# ESP32_Module.net
KiCad netlist of a schematic drawn in Altium Designer
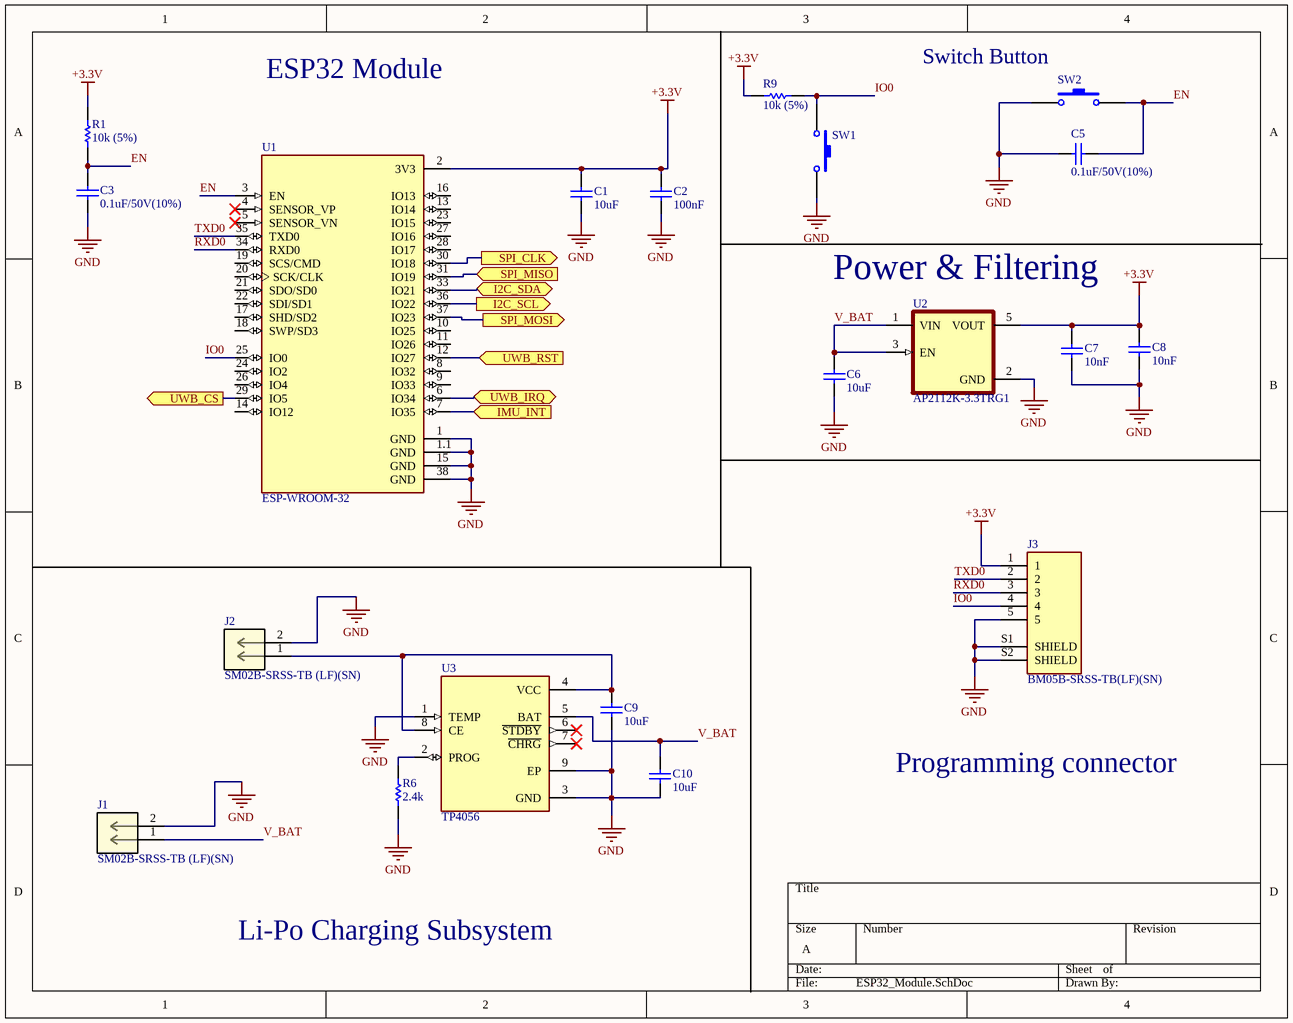
[diagram p0: ESP32_Module.SchDoc]

(export (version "E")
  (design (tool "Eeschema 10.0.6"))
  (components
    (comp (ref "C1")
      (value "10uF")
      (footprint "CAPC1608X90")
      (description "Capacitor")
      (fields (field (name "Comment") "Cap") (field (name "PUBLISHER") "Altium Limited"))
      (libsource (lib "Miscellaneous Devices") (part "Cap"))
    )
    (comp (ref "C2")
      (value "100nF")
      (footprint "CAPC1005X55N")
      (description "Capacitor")
      (fields (field (name "Comment") "Cap") (field (name "PUBLISHER") "Altium Limited"))
      (libsource (lib "Miscellaneous Devices") (part "Cap"))
    )
    (comp (ref "C3")
      (value "0.1uF/50V(10%)")
      (footprint "CAPC2012X94N")
      (description "Capacitor")
      (fields (field (name "Comment") "Cap") (field (name "PUBLISHER") "Altium Limited"))
      (libsource (lib "Miscellaneous Devices") (part "Cap"))
    )
    (comp (ref "C5")
      (value "0.1uF/50V(10%)")
      (footprint "CAPC2012X94N")
      (description "Capacitor")
      (fields (field (name "Comment") "Cap") (field (name "PUBLISHER") "Altium Limited"))
      (libsource (lib "Miscellaneous Devices") (part "Cap"))
    )
    (comp (ref "C6")
      (value "10uF")
      (footprint "CAPC1608X90")
      (description "Capacitor")
      (fields (field (name "Comment") "Cap") (field (name "PUBLISHER") "Altium Limited"))
      (libsource (lib "Miscellaneous Devices") (part "Cap"))
    )
    (comp (ref "C7")
      (value "10nF")
      (footprint "CAPC1608X87N")
      (description "Capacitor")
      (fields (field (name "Comment") "Cap") (field (name "PUBLISHER") "Altium Limited"))
      (libsource (lib "Miscellaneous Devices") (part "Cap"))
    )
    (comp (ref "C8")
      (value "10nF")
      (footprint "CAPC1608X87N")
      (description "Capacitor")
      (fields (field (name "Comment") "Cap") (field (name "PUBLISHER") "Altium Limited"))
      (libsource (lib "Miscellaneous Devices") (part "Cap"))
    )
    (comp (ref "C9")
      (value "10uF")
      (footprint "CAPC1608X90")
      (description "Capacitor")
      (fields (field (name "Comment") "Cap") (field (name "PUBLISHER") "Altium Limited"))
      (libsource (lib "Miscellaneous Devices") (part "Cap"))
    )
    (comp (ref "C10")
      (value "10uF")
      (footprint "CAPC1608X90")
      (description "Capacitor")
      (fields (field (name "Comment") "Cap") (field (name "PUBLISHER") "Altium Limited"))
      (libsource (lib "Miscellaneous Devices") (part "Cap"))
    )
    (comp (ref "J1")
      (value "SM02B-SRSS-TB (LF)(SN)")
      (footprint "CONN_SM02B-SRSS-TB_JST")
      (description "Description")
      (fields (field (name "COPYRIGHT") "Copyright (C) 2026 Ultra Librarian. All rights reserved."))
      (libsource (lib "SM02B-SRSS-TBLFSN") (part "SM02B-SRSS-TB LFSN"))
    )
    (comp (ref "J2")
      (value "SM02B-SRSS-TB (LF)(SN)")
      (footprint "CONN_SM02B-SRSS-TB_JST")
      (description "Description")
      (fields (field (name "COPYRIGHT") "Copyright (C) 2026 Ultra Librarian. All rights reserved."))
      (libsource (lib "SM02B-SRSS-TBLFSN") (part "SM02B-SRSS-TB LFSN"))
    )
    (comp (ref "J3")
      (value "BM05B-SRSS-TB(LF)(SN)")
      (footprint "JST_BM05B-SRSS-TB(LF)(SN)")
      (libsource (lib "BM05B-SRSS-TB_LF__SN_") (part "BM05B-SRSS-TB(LF)(SN)"))
    )
    (comp (ref "R1")
      (value "10k (5%)")
      (footprint "RESC1005X40")
      (description "Resistor")
      (fields (field (name "Comment") "Res1") (field (name "PUBLISHER") "Altium Limited"))
      (libsource (lib "Miscellaneous Devices") (part "Res1"))
    )
    (comp (ref "R6")
      (value "2.4k")
      (footprint "RESC1005X40N")
      (description "Resistor")
      (fields (field (name "Comment") "Res1") (field (name "PUBLISHER") "Altium Limited"))
      (libsource (lib "Miscellaneous Devices") (part "Res1"))
    )
    (comp (ref "R9")
      (value "10k (5%)")
      (footprint "RESC1005X40")
      (description "Resistor")
      (fields (field (name "Comment") "Res1") (field (name "PUBLISHER") "Altium Limited"))
      (libsource (lib "Miscellaneous Devices") (part "Res1"))
    )
    (comp (ref "SW1")
      (value "SW-PB")
      (footprint "SW_TL3342F160QG")
      (description "Switch")
      (fields (field (name "PUBLISHER") "Altium Limited"))
      (libsource (lib "Miscellaneous Devices") (part "SW-PB"))
    )
    (comp (ref "SW2")
      (value "SW-PB")
      (footprint "SW_TL3342F160QG")
      (description "Switch")
      (fields (field (name "PUBLISHER") "Altium Limited"))
      (libsource (lib "Miscellaneous Devices") (part "SW-PB"))
    )
    (comp (ref "U1")
      (value "ESP-WROOM-32")
      (footprint "MODULE_ESP-WROOM-32")
      (fields (field (name "MF") "Espressif Systems"))
      (libsource (lib "ESP-WROOM-32") (part "ESP-WROOM-32"))
    )
    (comp (ref "U2")
      (value "AP2112K-3.3TRG1")
      (footprint "SOT95P285X140-5N")
      (description "Linear Voltage Regulator IC Positive Fixed 1 Output 600mA SOT-25")
      (fields (field (name "MF") "Diodes Inc."))
      (libsource (lib "AP2112K-3.3TRG1") (part "AP2112K-3.3TRG1"))
    )
    (comp (ref "U3")
      (value "TP4056")
      (footprint "SOP127P600X175-9N")
      (description "Complete single cell Li-Ion battery with a constant current / constant voltage linear charger")
      (fields (field (name "MF") "NanJing Top Power ASIC Corp."))
      (libsource (lib "TP4056") (part "TP4056"))
    )
  )
  (nets
    (net (code "1") (name "+3.3V") (class "Default")
      (node (ref "C1") (pin "2") (pinfunction "2_2") (pintype "passive"))
      (node (ref "C2") (pin "2") (pinfunction "2_2") (pintype "passive"))
      (node (ref "C7") (pin "2") (pinfunction "2_2") (pintype "passive"))
      (node (ref "C8") (pin "2") (pinfunction "2_2") (pintype "passive"))
      (node (ref "J3") (pin "1") (pinfunction "1_1") (pintype "passive"))
      (node (ref "R1") (pin "2") (pinfunction "2_2") (pintype "passive"))
      (node (ref "R9") (pin "2") (pinfunction "2_2") (pintype "passive"))
      (node (ref "U1") (pin "2") (pinfunction "3V3_2") (pintype "power_in"))
      (node (ref "U2") (pin "5") (pinfunction "VOUT_5") (pintype "power_in"))
    )
    (net (code "2") (name "/EN") (class "Default")
      (node (ref "C3") (pin "2") (pinfunction "2_2") (pintype "passive"))
      (node (ref "C5") (pin "2") (pinfunction "2_2") (pintype "passive"))
      (node (ref "R1") (pin "1") (pinfunction "1_1") (pintype "passive"))
      (node (ref "SW2") (pin "2") (pinfunction "2_2") (pintype "passive"))
      (node (ref "U1") (pin "3") (pinfunction "EN_3") (pintype "input"))
    )
    (net (code "3") (name "/I2C_SCL") (class "Default")
      (node (ref "U1") (pin "36") (pinfunction "IO22_36") (pintype "bidirectional"))
    )
    (net (code "4") (name "/I2C_SDA") (class "Default")
      (node (ref "U1") (pin "33") (pinfunction "IO21_33") (pintype "bidirectional"))
    )
    (net (code "5") (name "/IMU_INT") (class "Default")
      (node (ref "U1") (pin "7") (pinfunction "IO35_7") (pintype "bidirectional"))
    )
    (net (code "6") (name "/IO0") (class "Default")
      (node (ref "J3") (pin "4") (pinfunction "4_4") (pintype "passive"))
      (node (ref "R9") (pin "1") (pinfunction "1_1") (pintype "passive"))
      (node (ref "SW1") (pin "1") (pinfunction "1_1") (pintype "passive"))
      (node (ref "U1") (pin "25") (pinfunction "IO0_25") (pintype "bidirectional"))
    )
    (net (code "7") (name "/RXD0") (class "Default")
      (node (ref "J3") (pin "3") (pinfunction "3_3") (pintype "passive"))
      (node (ref "U1") (pin "34") (pinfunction "RXD0_34") (pintype "bidirectional"))
    )
    (net (code "8") (name "/SPI_CLK") (class "Default")
      (node (ref "U1") (pin "30") (pinfunction "IO18_30") (pintype "bidirectional"))
    )
    (net (code "9") (name "/SPI_MISO") (class "Default")
      (node (ref "U1") (pin "31") (pinfunction "IO19_31") (pintype "bidirectional"))
    )
    (net (code "10") (name "/SPI_MOSI") (class "Default")
      (node (ref "U1") (pin "37") (pinfunction "IO23_37") (pintype "bidirectional"))
    )
    (net (code "11") (name "/TXD0") (class "Default")
      (node (ref "J3") (pin "2") (pinfunction "2_2") (pintype "passive"))
      (node (ref "U1") (pin "35") (pinfunction "TXD0_35") (pintype "bidirectional"))
    )
    (net (code "12") (name "/UWB_CS") (class "Default")
      (node (ref "U1") (pin "29") (pinfunction "IO5_29") (pintype "bidirectional"))
    )
    (net (code "13") (name "/UWB_IRQ") (class "Default")
      (node (ref "U1") (pin "6") (pinfunction "IO34_6") (pintype "bidirectional"))
    )
    (net (code "14") (name "/UWB_RST") (class "Default")
      (node (ref "U1") (pin "12") (pinfunction "IO27_12") (pintype "bidirectional"))
    )
    (net (code "15") (name "/V_BAT") (class "Default")
      (node (ref "C10") (pin "2") (pinfunction "2_2") (pintype "passive"))
      (node (ref "C6") (pin "2") (pinfunction "2_2") (pintype "passive"))
      (node (ref "J1") (pin "1") (pinfunction "1_1") (pintype "passive"))
      (node (ref "U2") (pin "1") (pinfunction "VIN_1") (pintype "power_in"))
      (node (ref "U2") (pin "3") (pinfunction "EN_3") (pintype "input"))
      (node (ref "U3") (pin "5") (pinfunction "BAT_5") (pintype "power_in"))
    )
    (net (code "16") (name "GND") (class "Default")
      (node (ref "C1") (pin "1") (pinfunction "1_1") (pintype "passive"))
      (node (ref "C10") (pin "1") (pinfunction "1_1") (pintype "passive"))
      (node (ref "C2") (pin "1") (pinfunction "1_1") (pintype "passive"))
      (node (ref "C3") (pin "1") (pinfunction "1_1") (pintype "passive"))
      (node (ref "C5") (pin "1") (pinfunction "1_1") (pintype "passive"))
      (node (ref "C6") (pin "1") (pinfunction "1_1") (pintype "passive"))
      (node (ref "C7") (pin "1") (pinfunction "1_1") (pintype "passive"))
      (node (ref "C8") (pin "1") (pinfunction "1_1") (pintype "passive"))
      (node (ref "C9") (pin "1") (pinfunction "1_1") (pintype "passive"))
      (node (ref "J1") (pin "2") (pinfunction "2_2") (pintype "passive"))
      (node (ref "J2") (pin "2") (pinfunction "2_2") (pintype "passive"))
      (node (ref "J3") (pin "5") (pinfunction "5_5") (pintype "passive"))
      (node (ref "J3") (pin "S1") (pinfunction "SHIELD_S1") (pintype "passive"))
      (node (ref "J3") (pin "S2") (pinfunction "SHIELD_S2") (pintype "passive"))
      (node (ref "R6") (pin "1") (pinfunction "1_1") (pintype "passive"))
      (node (ref "SW1") (pin "2") (pinfunction "2_2") (pintype "passive"))
      (node (ref "SW2") (pin "1") (pinfunction "1_1") (pintype "passive"))
      (node (ref "U1") (pin "1") (pinfunction "GND_1") (pintype "power_in"))
      (node (ref "U1") (pin "1.1") (pinfunction "GND_1.1") (pintype "power_in"))
      (node (ref "U1") (pin "15") (pinfunction "GND_15") (pintype "power_in"))
      (node (ref "U1") (pin "38") (pinfunction "GND_38") (pintype "power_in"))
      (node (ref "U2") (pin "2") (pinfunction "GND_2") (pintype "power_in"))
      (node (ref "U3") (pin "1") (pinfunction "TEMP_1") (pintype "input"))
      (node (ref "U3") (pin "3") (pinfunction "GND_3") (pintype "power_in"))
      (node (ref "U3") (pin "9") (pinfunction "EP_9") (pintype "passive"))
    )
    (net (code "17") (name "Net-(U3-CE)") (class "Default")
      (node (ref "C9") (pin "2") (pinfunction "2_2") (pintype "passive"))
      (node (ref "J2") (pin "1") (pinfunction "1_1") (pintype "passive"))
      (node (ref "U3") (pin "4") (pinfunction "VCC_4") (pintype "power_in"))
      (node (ref "U3") (pin "8") (pinfunction "CE_8") (pintype "input"))
    )
    (net (code "18") (name "Net-(U3-PROG)") (class "Default")
      (node (ref "R6") (pin "2") (pinfunction "2_2") (pintype "passive"))
      (node (ref "U3") (pin "2") (pinfunction "PROG_2") (pintype "bidirectional"))
    )
    (net (code "19") (name "unconnected-(U1-IO2-Pad24)") (class "Default")
      (node (ref "U1") (pin "24") (pinfunction "IO2_24") (pintype "bidirectional"))
    )
    (net (code "20") (name "unconnected-(U1-IO4-Pad26)") (class "Default")
      (node (ref "U1") (pin "26") (pinfunction "IO4_26") (pintype "bidirectional"))
    )
    (net (code "21") (name "unconnected-(U1-IO12-Pad14)") (class "Default")
      (node (ref "U1") (pin "14") (pinfunction "IO12_14") (pintype "bidirectional"))
    )
    (net (code "22") (name "unconnected-(U1-IO13-Pad16)") (class "Default")
      (node (ref "U1") (pin "16") (pinfunction "IO13_16") (pintype "bidirectional"))
    )
    (net (code "23") (name "unconnected-(U1-IO14-Pad13)") (class "Default")
      (node (ref "U1") (pin "13") (pinfunction "IO14_13") (pintype "bidirectional"))
    )
    (net (code "24") (name "unconnected-(U1-IO15-Pad23)") (class "Default")
      (node (ref "U1") (pin "23") (pinfunction "IO15_23") (pintype "bidirectional"))
    )
    (net (code "25") (name "unconnected-(U1-IO16-Pad27)") (class "Default")
      (node (ref "U1") (pin "27") (pinfunction "IO16_27") (pintype "bidirectional"))
    )
    (net (code "26") (name "unconnected-(U1-IO17-Pad28)") (class "Default")
      (node (ref "U1") (pin "28") (pinfunction "IO17_28") (pintype "bidirectional"))
    )
    (net (code "27") (name "unconnected-(U1-IO25-Pad10)") (class "Default")
      (node (ref "U1") (pin "10") (pinfunction "IO25_10") (pintype "bidirectional"))
    )
    (net (code "28") (name "unconnected-(U1-IO26-Pad11)") (class "Default")
      (node (ref "U1") (pin "11") (pinfunction "IO26_11") (pintype "bidirectional"))
    )
    (net (code "29") (name "unconnected-(U1-IO32-Pad8)") (class "Default")
      (node (ref "U1") (pin "8") (pinfunction "IO32_8") (pintype "bidirectional"))
    )
    (net (code "30") (name "unconnected-(U1-IO33-Pad9)") (class "Default")
      (node (ref "U1") (pin "9") (pinfunction "IO33_9") (pintype "bidirectional"))
    )
    (net (code "31") (name "unconnected-(U1-SCK{slash}CLK-Pad20)") (class "Default")
      (node (ref "U1") (pin "20") (pinfunction "SCK/CLK_20") (pintype "bidirectional"))
    )
    (net (code "32") (name "unconnected-(U1-SCS{slash}CMD-Pad19)") (class "Default")
      (node (ref "U1") (pin "19") (pinfunction "SCS/CMD_19") (pintype "bidirectional"))
    )
    (net (code "33") (name "unconnected-(U1-SDI{slash}SD1-Pad22)") (class "Default")
      (node (ref "U1") (pin "22") (pinfunction "SDI/SD1_22") (pintype "bidirectional"))
    )
    (net (code "34") (name "unconnected-(U1-SDO{slash}SD0-Pad21)") (class "Default")
      (node (ref "U1") (pin "21") (pinfunction "SDO/SD0_21") (pintype "bidirectional"))
    )
    (net (code "35") (name "unconnected-(U1-SENSOR_VN-Pad5)") (class "Default")
      (node (ref "U1") (pin "5") (pinfunction "SENSOR_VN_5") (pintype "input+no_connect"))
    )
    (net (code "36") (name "unconnected-(U1-SENSOR_VP-Pad4)") (class "Default")
      (node (ref "U1") (pin "4") (pinfunction "SENSOR_VP_4") (pintype "input+no_connect"))
    )
    (net (code "37") (name "unconnected-(U1-SHD{slash}SD2-Pad17)") (class "Default")
      (node (ref "U1") (pin "17") (pinfunction "SHD/SD2_17") (pintype "bidirectional"))
    )
    (net (code "38") (name "unconnected-(U1-SWP{slash}SD3-Pad18)") (class "Default")
      (node (ref "U1") (pin "18") (pinfunction "SWP/SD3_18") (pintype "bidirectional"))
    )
    (net (code "39") (name "unconnected-(U3-~{CHRG}-Pad7)") (class "Default")
      (node (ref "U3") (pin "7") (pinfunction "~{CHRG}_7") (pintype "output+no_connect"))
    )
    (net (code "40") (name "unconnected-(U3-~{STDBY}-Pad6)") (class "Default")
      (node (ref "U3") (pin "6") (pinfunction "~{STDBY}_6") (pintype "output+no_connect"))
    )
  )
)
